# Copy_of_untitled.net
KiCad netlist of a schematic drawn in EAGLE
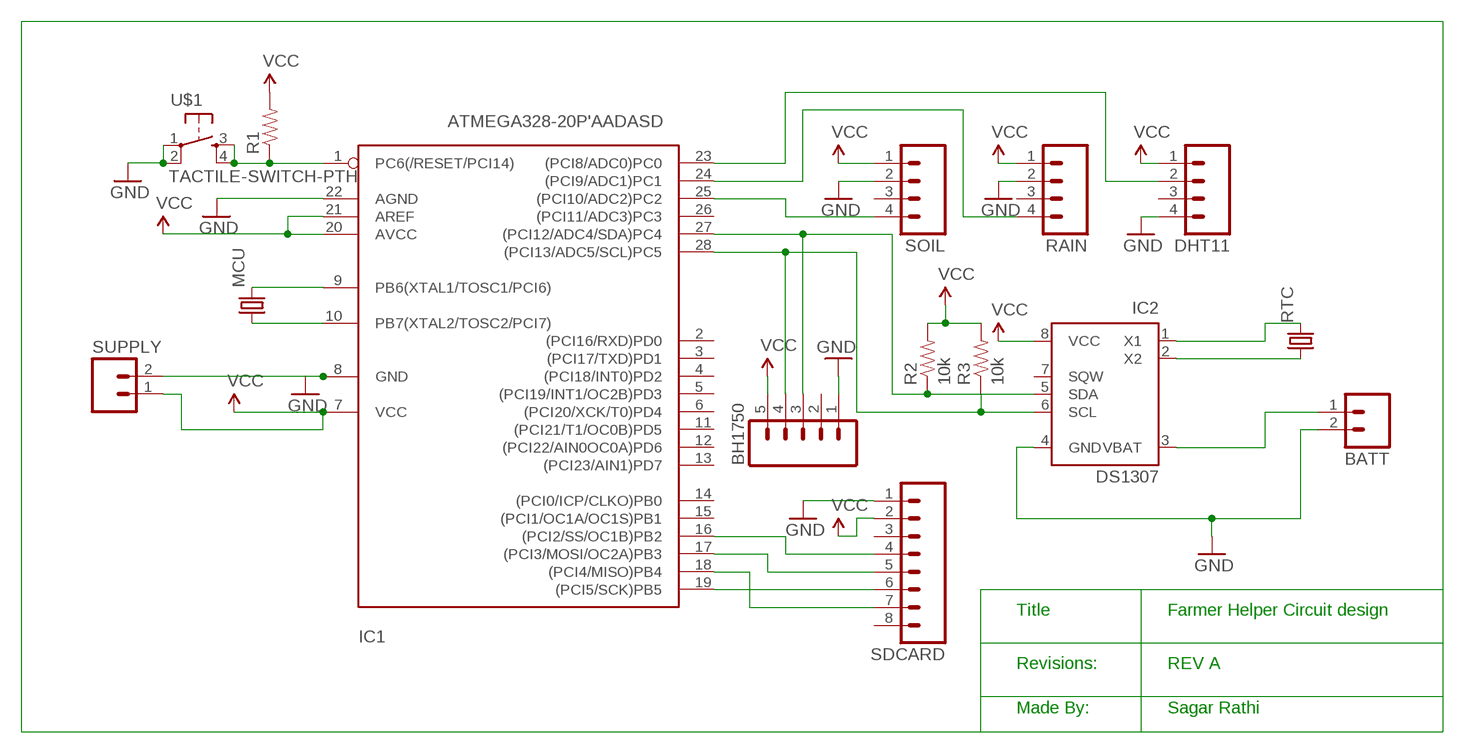
[diagram p0: schematic, sheet 1]

(export (version "E")
  (design (tool "Eeschema 10.0.6"))
  (components
    (comp (ref "BATT")
      (value "M02PTH3")
      (footprint "eagle-import:1X02_LONGPADS")
      (libsource (lib "eagle-import") (part "M02PTH3"))
    )
    (comp (ref "BH1750")
      (value "M05LOCK_LONGPADS")
      (footprint "eagle-import:1X05_LOCK_LONGPADS")
      (libsource (lib "eagle-import") (part "M05LOCK_LONGPADS"))
    )
    (comp (ref "DHT11")
      (value "M04LONGPADS")
      (footprint "eagle-import:1X04_LONGPADS")
      (libsource (lib "eagle-import") (part "M04LONGPADS"))
    )
    (comp (ref "IC1")
      (value "ATMEGA328-20P'AADASD")
      (footprint "eagle-import:DIL28-3")
      (libsource (lib "eagle-import") (part "ATMEGA328P'AADASD-20"))
    )
    (comp (ref "IC2")
      (value "DS1307")
      (footprint "eagle-import:DIP-8")
      (libsource (lib "eagle-import") (part "DS1307"))
    )
    (comp (ref "MCU")
      (value "CRYSTALTC38H")
      (footprint "eagle-import:TC38H")
      (libsource (lib "eagle-import") (part "CRYSTALTC38H"))
    )
    (comp (ref "R1")
      (value "RESISTORAXIAL-0.3")
      (footprint "eagle-import:AXIAL-0.3")
      (libsource (lib "eagle-import") (part "RESISTORAXIAL-0.3"))
    )
    (comp (ref "R2")
      (value "10k")
      (footprint "eagle-import:AXIAL-0.3")
      (libsource (lib "eagle-import") (part "10KOHM-1/4W-1%(PTH)HORIZ"))
    )
    (comp (ref "R3")
      (value "10k")
      (footprint "eagle-import:AXIAL-0.3")
      (libsource (lib "eagle-import") (part "10KOHM-1/4W-1%(PTH)HORIZ"))
    )
    (comp (ref "RAIN")
      (value "M04LONGPADS")
      (footprint "eagle-import:1X04_LONGPADS")
      (libsource (lib "eagle-import") (part "M04LONGPADS"))
    )
    (comp (ref "RTC")
      (value "CRYSTALTC26H_EZ")
      (footprint "eagle-import:TC26HEZ")
      (libsource (lib "eagle-import") (part "CRYSTALTC26H_EZ"))
    )
    (comp (ref "SDCARD")
      (value "M08LONGPADS")
      (footprint "eagle-import:1X08_LONGPADS")
      (libsource (lib "eagle-import") (part "M08LONGPADS"))
    )
    (comp (ref "SOIL")
      (value "M04LONGPADS")
      (footprint "eagle-import:1X04_LONGPADS")
      (libsource (lib "eagle-import") (part "M04LONGPADS"))
    )
    (comp (ref "SUPPLY")
      (value "M02PTH3")
      (footprint "eagle-import:1X02_LONGPADS")
      (libsource (lib "eagle-import") (part "M02PTH3"))
    )
    (comp (ref "U$1")
      (value "TACTILE-SWITCH-PTH")
      (footprint "eagle-import:TAC-SWITCH-PTH")
      (libsource (lib "eagle-import") (part "TACTILE-SWITCH-PTH"))
    )
  )
  (nets
    (net (code "1") (name "GND") (class "Default")
      (node (ref "BATT") (pin "2") (pinfunction "2_2") (pintype "passive"))
      (node (ref "BH1750") (pin "1") (pinfunction "1_1") (pintype "passive"))
      (node (ref "DHT11") (pin "4") (pinfunction "4_4") (pintype "passive"))
      (node (ref "IC1") (pin "22") (pinfunction "AGND_22") (pintype "bidirectional"))
      (node (ref "IC1") (pin "8") (pinfunction "GND_8") (pintype "bidirectional"))
      (node (ref "IC2") (pin "4") (pinfunction "GND_4") (pintype "power_in"))
      (node (ref "RAIN") (pin "2") (pinfunction "2_2") (pintype "passive"))
      (node (ref "SDCARD") (pin "1") (pinfunction "1_1") (pintype "passive"))
      (node (ref "SOIL") (pin "2") (pinfunction "2_2") (pintype "passive"))
      (node (ref "SUPPLY") (pin "2") (pinfunction "2_2") (pintype "passive"))
      (node (ref "U$1") (pin "1") (pinfunction "1_1") (pintype "passive"))
      (node (ref "U$1") (pin "2") (pinfunction "2_2") (pintype "passive"))
    )
    (net (code "2") (name "Net-(IC1-(PCI2{slash}SS{slash}OC1B)PB2)") (class "Default")
      (node (ref "IC1") (pin "16") (pinfunction "(PCI2/SS/OC1B)PB2_16") (pintype "bidirectional"))
      (node (ref "SDCARD") (pin "4") (pinfunction "4_4") (pintype "passive"))
    )
    (net (code "3") (name "Net-(IC1-(PCI3{slash}MOSI{slash}OC2A)PB3)") (class "Default")
      (node (ref "IC1") (pin "17") (pinfunction "(PCI3/MOSI/OC2A)PB3_17") (pintype "bidirectional"))
      (node (ref "SDCARD") (pin "5") (pinfunction "5_5") (pintype "passive"))
    )
    (net (code "4") (name "Net-(IC1-(PCI4{slash}MISO)PB4)") (class "Default")
      (node (ref "IC1") (pin "18") (pinfunction "(PCI4/MISO)PB4_18") (pintype "bidirectional"))
      (node (ref "SDCARD") (pin "7") (pinfunction "7_7") (pintype "passive"))
    )
    (net (code "5") (name "Net-(IC1-(PCI5{slash}SCK)PB5)") (class "Default")
      (node (ref "IC1") (pin "19") (pinfunction "(PCI5/SCK)PB5_19") (pintype "bidirectional"))
      (node (ref "SDCARD") (pin "6") (pinfunction "6_6") (pintype "passive"))
    )
    (net (code "6") (name "Net-(IC1-(PCI8{slash}ADC0)PC0)") (class "Default")
      (node (ref "DHT11") (pin "2") (pinfunction "2_2") (pintype "passive"))
      (node (ref "IC1") (pin "23") (pinfunction "(PCI8/ADC0)PC0_23") (pintype "bidirectional"))
    )
    (net (code "7") (name "Net-(IC1-(PCI9{slash}ADC1)PC1)") (class "Default")
      (node (ref "IC1") (pin "24") (pinfunction "(PCI9/ADC1)PC1_24") (pintype "bidirectional"))
      (node (ref "RAIN") (pin "4") (pinfunction "4_4") (pintype "passive"))
    )
    (net (code "8") (name "Net-(IC1-(PCI10{slash}ADC2)PC2)") (class "Default")
      (node (ref "IC1") (pin "25") (pinfunction "(PCI10/ADC2)PC2_25") (pintype "bidirectional"))
      (node (ref "SOIL") (pin "4") (pinfunction "4_4") (pintype "passive"))
    )
    (net (code "9") (name "Net-(IC1-(PCI12{slash}ADC4{slash}SDA)PC4)") (class "Default")
      (node (ref "BH1750") (pin "3") (pinfunction "3_3") (pintype "passive"))
      (node (ref "IC1") (pin "27") (pinfunction "(PCI12/ADC4/SDA)PC4_27") (pintype "bidirectional"))
      (node (ref "IC2") (pin "5") (pinfunction "SDA_5") (pintype "output"))
      (node (ref "R2") (pin "P$1") (pinfunction "1_P$1") (pintype "passive"))
    )
    (net (code "10") (name "Net-(IC1-(PCI13{slash}ADC5{slash}SCL)PC5)") (class "Default")
      (node (ref "BH1750") (pin "4") (pinfunction "4_4") (pintype "passive"))
      (node (ref "IC1") (pin "28") (pinfunction "(PCI13/ADC5/SCL)PC5_28") (pintype "bidirectional"))
      (node (ref "IC2") (pin "6") (pinfunction "SCL_6") (pintype "input"))
      (node (ref "R3") (pin "P$1") (pinfunction "1_P$1") (pintype "passive"))
    )
    (net (code "11") (name "Net-(IC1-PB6(XTAL1{slash}TOSC1{slash}PCI6))") (class "Default")
      (node (ref "IC1") (pin "9") (pinfunction "PB6(XTAL1/TOSC1/PCI6)_9") (pintype "bidirectional"))
      (node (ref "MCU") (pin "2") (pinfunction "2_2") (pintype "passive"))
    )
    (net (code "12") (name "Net-(IC1-PB7(XTAL2{slash}TOSC2{slash}PCI7))") (class "Default")
      (node (ref "IC1") (pin "10") (pinfunction "PB7(XTAL2/TOSC2/PCI7)_10") (pintype "bidirectional"))
      (node (ref "MCU") (pin "1") (pinfunction "1_1") (pintype "passive"))
    )
    (net (code "13") (name "Net-(IC1-PC6({slash}RESET{slash}PCI14))") (class "Default")
      (node (ref "IC1") (pin "1") (pinfunction "PC6(/RESET/PCI14)_1") (pintype "bidirectional"))
      (node (ref "R1") (pin "P$1") (pinfunction "1_P$1") (pintype "passive"))
      (node (ref "U$1") (pin "3") (pinfunction "3_3") (pintype "passive"))
      (node (ref "U$1") (pin "4") (pinfunction "4_4") (pintype "passive"))
    )
    (net (code "14") (name "Net-(IC2-VBAT)") (class "Default")
      (node (ref "BATT") (pin "1") (pinfunction "1_1") (pintype "passive"))
      (node (ref "IC2") (pin "3") (pinfunction "VBAT_3") (pintype "input"))
    )
    (net (code "15") (name "Net-(IC2-X1)") (class "Default")
      (node (ref "IC2") (pin "1") (pinfunction "X1_1") (pintype "input"))
      (node (ref "RTC") (pin "2") (pinfunction "2_2") (pintype "passive"))
    )
    (net (code "16") (name "Net-(IC2-X2)") (class "Default")
      (node (ref "IC2") (pin "2") (pinfunction "X2_2") (pintype "input"))
      (node (ref "RTC") (pin "1") (pinfunction "1_1") (pintype "passive"))
    )
    (net (code "17") (name "VCC") (class "Default")
      (node (ref "BH1750") (pin "5") (pinfunction "5_5") (pintype "passive"))
      (node (ref "DHT11") (pin "1") (pinfunction "1_1") (pintype "passive"))
      (node (ref "IC1") (pin "20") (pinfunction "AVCC_20") (pintype "bidirectional"))
      (node (ref "IC1") (pin "21") (pinfunction "AREF_21") (pintype "bidirectional"))
      (node (ref "IC1") (pin "7") (pinfunction "VCC_7") (pintype "bidirectional"))
      (node (ref "IC2") (pin "8") (pinfunction "VCC_8") (pintype "power_in"))
      (node (ref "R1") (pin "P$2") (pinfunction "2_P$2") (pintype "passive"))
      (node (ref "R2") (pin "P$2") (pinfunction "2_P$2") (pintype "passive"))
      (node (ref "R3") (pin "P$2") (pinfunction "2_P$2") (pintype "passive"))
      (node (ref "RAIN") (pin "1") (pinfunction "1_1") (pintype "passive"))
      (node (ref "SDCARD") (pin "2") (pinfunction "2_2") (pintype "passive"))
      (node (ref "SOIL") (pin "1") (pinfunction "1_1") (pintype "passive"))
      (node (ref "SUPPLY") (pin "1") (pinfunction "1_1") (pintype "passive"))
    )
    (net (code "18") (name "unconnected-(BH1750-Pad2)") (class "Default")
      (node (ref "BH1750") (pin "2") (pinfunction "2_2") (pintype "passive"))
    )
    (net (code "19") (name "unconnected-(DHT11-Pad3)") (class "Default")
      (node (ref "DHT11") (pin "3") (pinfunction "3_3") (pintype "passive"))
    )
    (net (code "20") (name "unconnected-(IC1-(PCI0{slash}ICP{slash}CLKO)PB0-Pad14)") (class "Default")
      (node (ref "IC1") (pin "14") (pinfunction "(PCI0/ICP/CLKO)PB0_14") (pintype "bidirectional"))
    )
    (net (code "21") (name "unconnected-(IC1-(PCI1{slash}OC1A{slash}OC1S)PB1-Pad15)") (class "Default")
      (node (ref "IC1") (pin "15") (pinfunction "(PCI1/OC1A/OC1S)PB1_15") (pintype "bidirectional"))
    )
    (net (code "22") (name "unconnected-(IC1-(PCI11{slash}ADC3)PC3-Pad26)") (class "Default")
      (node (ref "IC1") (pin "26") (pinfunction "(PCI11/ADC3)PC3_26") (pintype "bidirectional"))
    )
    (net (code "23") (name "unconnected-(IC1-(PCI16{slash}RXD)PD0-Pad2)") (class "Default")
      (node (ref "IC1") (pin "2") (pinfunction "(PCI16/RXD)PD0_2") (pintype "bidirectional"))
    )
    (net (code "24") (name "unconnected-(IC1-(PCI17{slash}TXD)PD1-Pad3)") (class "Default")
      (node (ref "IC1") (pin "3") (pinfunction "(PCI17/TXD)PD1_3") (pintype "bidirectional"))
    )
    (net (code "25") (name "unconnected-(IC1-(PCI18{slash}INT0)PD2-Pad4)") (class "Default")
      (node (ref "IC1") (pin "4") (pinfunction "(PCI18/INT0)PD2_4") (pintype "bidirectional"))
    )
    (net (code "26") (name "unconnected-(IC1-(PCI19{slash}INT1{slash}OC2B)PD3-Pad5)") (class "Default")
      (node (ref "IC1") (pin "5") (pinfunction "(PCI19/INT1/OC2B)PD3_5") (pintype "bidirectional"))
    )
    (net (code "27") (name "unconnected-(IC1-(PCI20{slash}XCK{slash}T0)PD4-Pad6)") (class "Default")
      (node (ref "IC1") (pin "6") (pinfunction "(PCI20/XCK/T0)PD4_6") (pintype "bidirectional"))
    )
    (net (code "28") (name "unconnected-(IC1-(PCI21{slash}T1{slash}OC0B)PD5-Pad11)") (class "Default")
      (node (ref "IC1") (pin "11") (pinfunction "(PCI21/T1/OC0B)PD5_11") (pintype "bidirectional"))
    )
    (net (code "29") (name "unconnected-(IC1-(PCI22{slash}AIN0OC0A)PD6-Pad12)") (class "Default")
      (node (ref "IC1") (pin "12") (pinfunction "(PCI22/AIN0OC0A)PD6_12") (pintype "bidirectional"))
    )
    (net (code "30") (name "unconnected-(IC1-(PCI23{slash}AIN1)PD7-Pad13)") (class "Default")
      (node (ref "IC1") (pin "13") (pinfunction "(PCI23/AIN1)PD7_13") (pintype "bidirectional"))
    )
    (net (code "31") (name "unconnected-(IC2-SQW-Pad7)") (class "Default")
      (node (ref "IC2") (pin "7") (pinfunction "SQW_7") (pintype "input"))
    )
    (net (code "32") (name "unconnected-(RAIN-Pad3)") (class "Default")
      (node (ref "RAIN") (pin "3") (pinfunction "3_3") (pintype "passive"))
    )
    (net (code "33") (name "unconnected-(SDCARD-Pad3)") (class "Default")
      (node (ref "SDCARD") (pin "3") (pinfunction "3_3") (pintype "passive"))
    )
    (net (code "34") (name "unconnected-(SDCARD-Pad8)") (class "Default")
      (node (ref "SDCARD") (pin "8") (pinfunction "8_8") (pintype "passive"))
    )
    (net (code "35") (name "unconnected-(SOIL-Pad3)") (class "Default")
      (node (ref "SOIL") (pin "3") (pinfunction "3_3") (pintype "passive"))
    )
  )
)
